# LIXIE_II_Main_V3.net
KiCad netlist of a schematic drawn in EAGLE
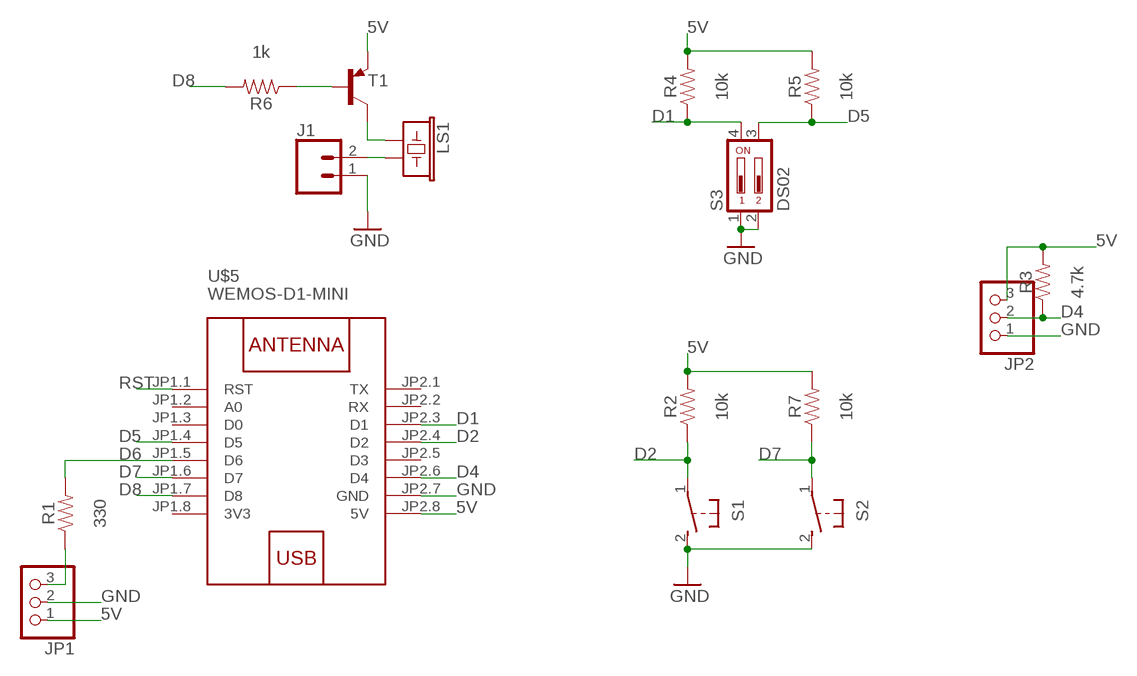
[diagram p0: schematic, sheet 1]

(export (version "E")
  (design (tool "Eeschema 10.0.6"))
  (components
    (comp (ref "J1")
      (value "CONN_02")
      (footprint "eagle-import:1X02")
      (libsource (lib "eagle-import") (part "CONN_02"))
    )
    (comp (ref "JP1")
      (value "PINHD-1X3")
      (footprint "eagle-import:1X03")
      (libsource (lib "eagle-import") (part "PINHD-1X3"))
    )
    (comp (ref "JP2")
      (value "PINHD-1X3")
      (footprint "eagle-import:1X03")
      (libsource (lib "eagle-import") (part "PINHD-1X3"))
    )
    (comp (ref "LS1")
      (value "BUZZER-PTH")
      (footprint "eagle-import:BUZZER-12MM")
      (libsource (lib "eagle-import") (part "BUZZER-PTH"))
    )
    (comp (ref "R1")
      (value "330")
      (footprint "eagle-import:0805")
      (libsource (lib "eagle-import") (part "0.3OHM-0805-1/8W-1%"))
    )
    (comp (ref "R2")
      (value "10k")
      (footprint "eagle-import:0805")
      (libsource (lib "eagle-import") (part "0.3OHM-0805-1/8W-1%"))
    )
    (comp (ref "R3")
      (value "4.7k")
      (footprint "eagle-import:0805")
      (libsource (lib "eagle-import") (part "0.3OHM-0805-1/8W-1%"))
    )
    (comp (ref "R4")
      (value "10k")
      (footprint "eagle-import:0805")
      (libsource (lib "eagle-import") (part "0.3OHM-0805-1/8W-1%"))
    )
    (comp (ref "R5")
      (value "10k")
      (footprint "eagle-import:0805")
      (libsource (lib "eagle-import") (part "0.3OHM-0805-1/8W-1%"))
    )
    (comp (ref "R6")
      (value "1k")
      (footprint "eagle-import:0805")
      (libsource (lib "eagle-import") (part "0.3OHM-0805-1/8W-1%"))
    )
    (comp (ref "R7")
      (value "10k")
      (footprint "eagle-import:0805")
      (libsource (lib "eagle-import") (part "0.3OHM-0805-1/8W-1%"))
    )
    (comp (ref "S1")
      (value "31-XX")
      (footprint "eagle-import:B3F-31XX")
      (libsource (lib "eagle-import") (part "31-XX"))
    )
    (comp (ref "S2")
      (value "31-XX")
      (footprint "eagle-import:B3F-31XX")
      (libsource (lib "eagle-import") (part "31-XX"))
    )
    (comp (ref "S3")
      (value "DS02")
      (footprint "eagle-import:DS-02")
      (fields (field (name "MPN") "MCNDS02"))
      (libsource (lib "eagle-import") (part "DS02"))
    )
    (comp (ref "T1")
      (value "-PNP-SOT23-EBC")
      (footprint "eagle-import:SOT23-EBC")
      (libsource (lib "eagle-import") (part "-PNP-SOT23-EBC"))
    )
    (comp (ref "U$5")
      (value "WEMOS-D1-MINI")
      (footprint "eagle-import:WEMOS-D1-MINI")
      (libsource (lib "eagle-import") (part "WEMOS-D1-MINI"))
    )
  )
  (nets
    (net (code "1") (name "/3V3") (class "Default")
      (node (ref "U$5") (pin "JP1.8") (pinfunction "3V3_JP1.8") (pintype "power_in"))
    )
    (net (code "2") (name "/5V") (class "Default")
      (node (ref "JP1") (pin "1") (pinfunction "1_1") (pintype "passive"))
      (node (ref "JP2") (pin "3") (pinfunction "3_3") (pintype "passive"))
      (node (ref "R2") (pin "2") (pinfunction "2_2") (pintype "passive"))
      (node (ref "R3") (pin "2") (pinfunction "2_2") (pintype "passive"))
      (node (ref "R4") (pin "2") (pinfunction "2_2") (pintype "passive"))
      (node (ref "R5") (pin "2") (pinfunction "2_2") (pintype "passive"))
      (node (ref "R7") (pin "2") (pinfunction "2_2") (pintype "passive"))
      (node (ref "T1") (pin "E") (pinfunction "E_E") (pintype "passive"))
      (node (ref "U$5") (pin "JP2.8") (pinfunction "5V_JP2.8") (pintype "power_in"))
    )
    (net (code "3") (name "/D1") (class "Default")
      (node (ref "R4") (pin "1") (pinfunction "1_1") (pintype "passive"))
      (node (ref "S3") (pin "4") (pinfunction "4_4") (pintype "passive"))
      (node (ref "U$5") (pin "JP2.3") (pinfunction "D1_JP2.3") (pintype "bidirectional"))
    )
    (net (code "4") (name "/D2") (class "Default")
      (node (ref "R2") (pin "1") (pinfunction "1_1") (pintype "passive"))
      (node (ref "S1") (pin "1") (pinfunction "P_1") (pintype "passive"))
      (node (ref "U$5") (pin "JP2.4") (pinfunction "D2_JP2.4") (pintype "bidirectional"))
    )
    (net (code "5") (name "/D4") (class "Default")
      (node (ref "JP2") (pin "2") (pinfunction "2_2") (pintype "passive"))
      (node (ref "R3") (pin "1") (pinfunction "1_1") (pintype "passive"))
      (node (ref "U$5") (pin "JP2.6") (pinfunction "D4_JP2.6") (pintype "bidirectional"))
    )
    (net (code "6") (name "/D5") (class "Default")
      (node (ref "R5") (pin "1") (pinfunction "1_1") (pintype "passive"))
      (node (ref "S3") (pin "3") (pinfunction "3_3") (pintype "passive"))
      (node (ref "U$5") (pin "JP1.4") (pinfunction "D5_JP1.4") (pintype "bidirectional"))
    )
    (net (code "7") (name "/D6") (class "Default")
      (node (ref "R1") (pin "2") (pinfunction "2_2") (pintype "passive"))
      (node (ref "U$5") (pin "JP1.5") (pinfunction "D6_JP1.5") (pintype "bidirectional"))
    )
    (net (code "8") (name "/D7") (class "Default")
      (node (ref "R7") (pin "1") (pinfunction "1_1") (pintype "passive"))
      (node (ref "S2") (pin "1") (pinfunction "P_1") (pintype "passive"))
      (node (ref "U$5") (pin "JP1.6") (pinfunction "D7_JP1.6") (pintype "bidirectional"))
    )
    (net (code "9") (name "/D8") (class "Default")
      (node (ref "R6") (pin "2") (pinfunction "2_2") (pintype "passive"))
      (node (ref "U$5") (pin "JP1.7") (pinfunction "D8_JP1.7") (pintype "bidirectional"))
    )
    (net (code "10") (name "/RST") (class "Default")
      (node (ref "U$5") (pin "JP1.1") (pinfunction "RST_JP1.1") (pintype "bidirectional"))
    )
    (net (code "11") (name "GND") (class "Default")
      (node (ref "J1") (pin "1") (pinfunction "1_1") (pintype "passive"))
      (node (ref "JP1") (pin "2") (pinfunction "2_2") (pintype "passive"))
      (node (ref "JP2") (pin "1") (pinfunction "1_1") (pintype "passive"))
      (node (ref "S1") (pin "2") (pinfunction "S_2") (pintype "passive"))
      (node (ref "S2") (pin "2") (pinfunction "S_2") (pintype "passive"))
      (node (ref "S3") (pin "1") (pinfunction "1_1") (pintype "passive"))
      (node (ref "S3") (pin "2") (pinfunction "2_2") (pintype "passive"))
      (node (ref "U$5") (pin "JP2.7") (pinfunction "GND_JP2.7") (pintype "power_in"))
    )
    (net (code "12") (name "Net-(JP1-Pad3)") (class "Default")
      (node (ref "JP1") (pin "3") (pinfunction "3_3") (pintype "passive"))
      (node (ref "R1") (pin "1") (pinfunction "1_1") (pintype "passive"))
    )
    (net (code "13") (name "Net-(LS1-1)") (class "Default")
      (node (ref "LS1") (pin "+") (pinfunction "1_+") (pintype "passive"))
      (node (ref "T1") (pin "C") (pinfunction "C_C") (pintype "passive"))
    )
    (net (code "14") (name "Net-(LS1-2)") (class "Default")
      (node (ref "J1") (pin "2") (pinfunction "2_2") (pintype "passive"))
      (node (ref "LS1") (pin "-") (pinfunction "2_-") (pintype "passive"))
    )
    (net (code "15") (name "Net-(R6-Pad1)") (class "Default")
      (node (ref "R6") (pin "1") (pinfunction "1_1") (pintype "passive"))
      (node (ref "T1") (pin "B") (pinfunction "B_B") (pintype "passive"))
    )
    (net (code "16") (name "unconnected-(U$5-A0-PadJP1.2)") (class "Default")
      (node (ref "U$5") (pin "JP1.2") (pinfunction "A0_JP1.2") (pintype "bidirectional"))
    )
    (net (code "17") (name "unconnected-(U$5-D0-PadJP1.3)") (class "Default")
      (node (ref "U$5") (pin "JP1.3") (pinfunction "D0_JP1.3") (pintype "bidirectional"))
    )
    (net (code "18") (name "unconnected-(U$5-D3-PadJP2.5)") (class "Default")
      (node (ref "U$5") (pin "JP2.5") (pinfunction "D3_JP2.5") (pintype "bidirectional"))
    )
    (net (code "19") (name "unconnected-(U$5-RX-PadJP2.2)") (class "Default")
      (node (ref "U$5") (pin "JP2.2") (pinfunction "RX_JP2.2") (pintype "bidirectional"))
    )
    (net (code "20") (name "unconnected-(U$5-TX-PadJP2.1)") (class "Default")
      (node (ref "U$5") (pin "JP2.1") (pinfunction "TX_JP2.1") (pintype "bidirectional"))
    )
  )
)
